# Raspi.net
KiCad netlist of a schematic drawn in Altium Designer
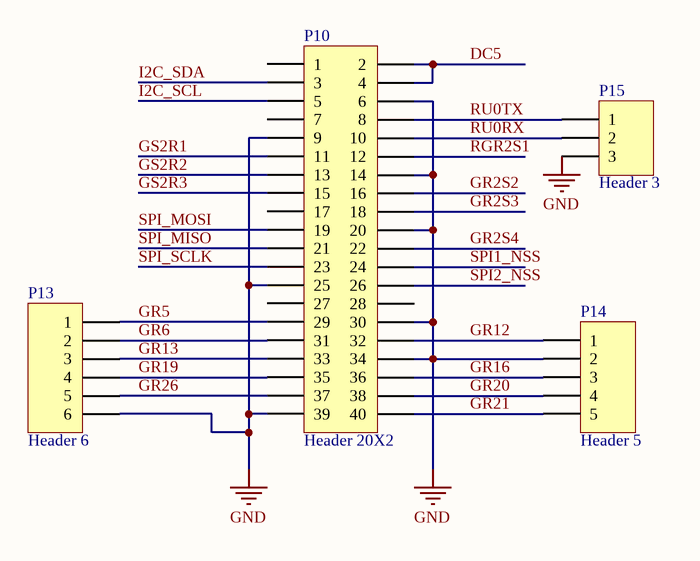
[diagram p0: Raspi.SchDoc]

(export (version "E")
  (design (tool "Eeschema 10.0.6"))
  (components
    (comp (ref "P10")
      (value "Header 20X2")
      (footprint "HDR2X20")
      (description "Header, 20-Pin, Dual row")
      (fields (field (name "PUBLISHER") "Altium Limited"))
      (libsource (lib "Miscellaneous Connectors") (part "Header 20X2"))
    )
    (comp (ref "P13")
      (value "Header 6")
      (footprint "HDR1X6")
      (description "Header, 6-Pin")
      (fields (field (name "PUBLISHER") "Altium Limited"))
      (libsource (lib "Miscellaneous Connectors") (part "Header 6"))
    )
    (comp (ref "P14")
      (value "Header 5")
      (footprint "HDR1X5")
      (description "Header, 5-Pin")
      (fields (field (name "PUBLISHER") "Altium Limited"))
      (libsource (lib "Miscellaneous Connectors") (part "Header 5"))
    )
    (comp (ref "P15")
      (value "Header 3")
      (footprint "HDR1X3")
      (description "Header, 3-Pin")
      (fields (field (name "PUBLISHER") "Altium Limited"))
      (libsource (lib "Miscellaneous Connectors") (part "Header 3"))
    )
  )
  (nets
    (net (code "1") (name "/DC5") (class "Default")
      (node (ref "P10") (pin "2") (pinfunction "2_2") (pintype "passive"))
      (node (ref "P10") (pin "4") (pinfunction "4_4") (pintype "passive"))
    )
    (net (code "2") (name "/GR2S2") (class "Default")
      (node (ref "P10") (pin "16") (pinfunction "16_16") (pintype "passive"))
    )
    (net (code "3") (name "/GR2S3") (class "Default")
      (node (ref "P10") (pin "18") (pinfunction "18_18") (pintype "passive"))
    )
    (net (code "4") (name "/GR2S4") (class "Default")
      (node (ref "P10") (pin "22") (pinfunction "22_22") (pintype "passive"))
    )
    (net (code "5") (name "/GR5") (class "Default")
      (node (ref "P10") (pin "29") (pinfunction "29_29") (pintype "passive"))
      (node (ref "P13") (pin "1") (pinfunction "1_1") (pintype "passive"))
    )
    (net (code "6") (name "/GR6") (class "Default")
      (node (ref "P10") (pin "31") (pinfunction "31_31") (pintype "passive"))
      (node (ref "P13") (pin "2") (pinfunction "2_2") (pintype "passive"))
    )
    (net (code "7") (name "/GR12") (class "Default")
      (node (ref "P10") (pin "32") (pinfunction "32_32") (pintype "passive"))
      (node (ref "P14") (pin "1") (pinfunction "1_1") (pintype "passive"))
    )
    (net (code "8") (name "/GR13") (class "Default")
      (node (ref "P10") (pin "33") (pinfunction "33_33") (pintype "passive"))
      (node (ref "P13") (pin "3") (pinfunction "3_3") (pintype "passive"))
    )
    (net (code "9") (name "/GR16") (class "Default")
      (node (ref "P10") (pin "36") (pinfunction "36_36") (pintype "passive"))
      (node (ref "P14") (pin "3") (pinfunction "3_3") (pintype "passive"))
    )
    (net (code "10") (name "/GR19") (class "Default")
      (node (ref "P10") (pin "35") (pinfunction "35_35") (pintype "passive"))
      (node (ref "P13") (pin "4") (pinfunction "4_4") (pintype "passive"))
    )
    (net (code "11") (name "/GR20") (class "Default")
      (node (ref "P10") (pin "38") (pinfunction "38_38") (pintype "passive"))
      (node (ref "P14") (pin "4") (pinfunction "4_4") (pintype "passive"))
    )
    (net (code "12") (name "/GR21") (class "Default")
      (node (ref "P10") (pin "40") (pinfunction "40_40") (pintype "passive"))
      (node (ref "P14") (pin "5") (pinfunction "5_5") (pintype "passive"))
    )
    (net (code "13") (name "/GR26") (class "Default")
      (node (ref "P10") (pin "37") (pinfunction "37_37") (pintype "passive"))
      (node (ref "P13") (pin "5") (pinfunction "5_5") (pintype "passive"))
    )
    (net (code "14") (name "/GS2R1") (class "Default")
      (node (ref "P10") (pin "11") (pinfunction "11_11") (pintype "passive"))
    )
    (net (code "15") (name "/GS2R2") (class "Default")
      (node (ref "P10") (pin "13") (pinfunction "13_13") (pintype "passive"))
    )
    (net (code "16") (name "/GS2R3") (class "Default")
      (node (ref "P10") (pin "15") (pinfunction "15_15") (pintype "passive"))
    )
    (net (code "17") (name "/I2C_SCL") (class "Default")
      (node (ref "P10") (pin "5") (pinfunction "5_5") (pintype "passive"))
    )
    (net (code "18") (name "/I2C_SDA") (class "Default")
      (node (ref "P10") (pin "3") (pinfunction "3_3") (pintype "passive"))
    )
    (net (code "19") (name "/RGR2S1") (class "Default")
      (node (ref "P10") (pin "12") (pinfunction "12_12") (pintype "passive"))
    )
    (net (code "20") (name "/RU0RX") (class "Default")
      (node (ref "P10") (pin "10") (pinfunction "10_10") (pintype "passive"))
      (node (ref "P15") (pin "2") (pinfunction "2_2") (pintype "passive"))
    )
    (net (code "21") (name "/RU0TX") (class "Default")
      (node (ref "P10") (pin "8") (pinfunction "8_8") (pintype "passive"))
      (node (ref "P15") (pin "1") (pinfunction "1_1") (pintype "passive"))
    )
    (net (code "22") (name "/SPI1_NSS") (class "Default")
      (node (ref "P10") (pin "24") (pinfunction "24_24") (pintype "passive"))
    )
    (net (code "23") (name "/SPI2_NSS") (class "Default")
      (node (ref "P10") (pin "26") (pinfunction "26_26") (pintype "passive"))
    )
    (net (code "24") (name "/SPI_MISO") (class "Default")
      (node (ref "P10") (pin "21") (pinfunction "21_21") (pintype "passive"))
    )
    (net (code "25") (name "/SPI_MOSI") (class "Default")
      (node (ref "P10") (pin "19") (pinfunction "19_19") (pintype "passive"))
    )
    (net (code "26") (name "/SPI_SCLK") (class "Default")
      (node (ref "P10") (pin "23") (pinfunction "23_23") (pintype "passive"))
    )
    (net (code "27") (name "GND") (class "Default")
      (node (ref "P10") (pin "14") (pinfunction "14_14") (pintype "passive"))
      (node (ref "P10") (pin "20") (pinfunction "20_20") (pintype "passive"))
      (node (ref "P10") (pin "25") (pinfunction "25_25") (pintype "passive"))
      (node (ref "P10") (pin "30") (pinfunction "30_30") (pintype "passive"))
      (node (ref "P10") (pin "34") (pinfunction "34_34") (pintype "passive"))
      (node (ref "P10") (pin "39") (pinfunction "39_39") (pintype "passive"))
      (node (ref "P10") (pin "6") (pinfunction "6_6") (pintype "passive"))
      (node (ref "P10") (pin "9") (pinfunction "9_9") (pintype "passive"))
      (node (ref "P13") (pin "6") (pinfunction "6_6") (pintype "passive"))
      (node (ref "P14") (pin "2") (pinfunction "2_2") (pintype "passive"))
      (node (ref "P15") (pin "3") (pinfunction "3_3") (pintype "passive"))
    )
    (net (code "28") (name "unconnected-(P10-Pad1)") (class "Default")
      (node (ref "P10") (pin "1") (pinfunction "1_1") (pintype "passive"))
    )
    (net (code "29") (name "unconnected-(P10-Pad7)") (class "Default")
      (node (ref "P10") (pin "7") (pinfunction "7_7") (pintype "passive"))
    )
    (net (code "30") (name "unconnected-(P10-Pad17)") (class "Default")
      (node (ref "P10") (pin "17") (pinfunction "17_17") (pintype "passive"))
    )
    (net (code "31") (name "unconnected-(P10-Pad27)") (class "Default")
      (node (ref "P10") (pin "27") (pinfunction "27_27") (pintype "passive"))
    )
    (net (code "32") (name "unconnected-(P10-Pad28)") (class "Default")
      (node (ref "P10") (pin "28") (pinfunction "28_28") (pintype "passive"))
    )
  )
)
